# Sender_TransmiterPower.net
KiCad netlist of a schematic drawn in Altium Designer
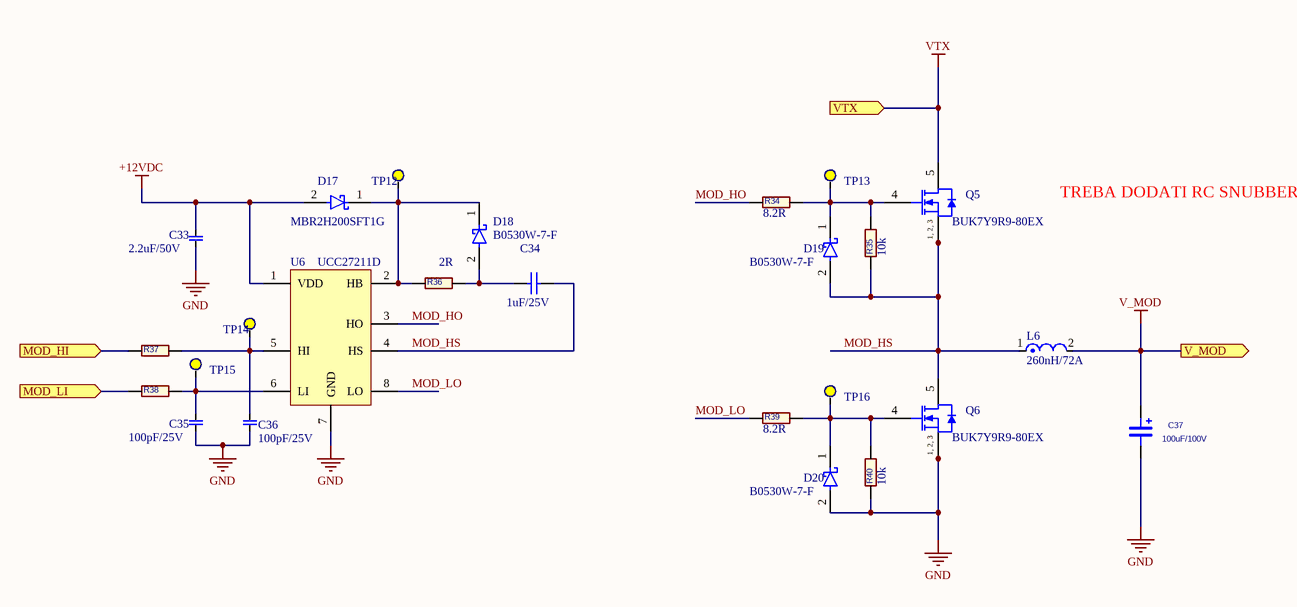
[diagram p0: Sender_TransmiterPower.SchDoc]

(export (version "E")
  (design (tool "Eeschema 10.0.6"))
  (components
    (comp (ref "C33")
      (value "2.2uF/50V")
      (footprint "FP-CL31-IPC_B")
      (description "Cap Ceramic 2.2uF 50V X7R ±10% SMD 1206 +125°C Embossed T/R")
      (fields (field (name "TOLERANCE") "10%"))
      (libsource (lib "New_Library") (part "CL31B225KBHVPNE"))
    )
    (comp (ref "C34")
      (value "1uF/25V")
      (footprint "CAPC2013X70X45LL10T25")
      (description "1µF ±10% 25V Ceramic Capacitor X5R 0805 (2012 Metric)")
      (fields (field (name "MANUFACTURER") "Murata") (field (name "PART NUMBER") "GRM216R61E105KA12D"))
      (libsource (lib "New_Library") (part "GRM216R61E105KA12D"))
    )
    (comp (ref "C35")
      (value "100pF/25V")
      (footprint "C-0603")
      (description "100pF ±5% 25V Ceramic Capacitor C0G, NP0 0201 (0603 Metric)")
      (fields
        (field (name "MANUFACTURER") "KEMET")
        (field (name "MANUFACTURER PART NUMBER") "C0201C101J3GACTU")
      )
      (libsource (lib "New_Library") (part "C0201C101J3GACTU"))
    )
    (comp (ref "C36")
      (value "100pF/25V")
      (footprint "C-0603")
      (description "100pF ±5% 25V Ceramic Capacitor C0G, NP0 0201 (0603 Metric)")
      (fields
        (field (name "MANUFACTURER") "KEMET")
        (field (name "MANUFACTURER PART NUMBER") "C0201C101J3GACTU")
      )
      (libsource (lib "New_Library") (part "C0201C101J3GACTU"))
    )
    (comp (ref "C37")
      (value "100uF/100V")
      (footprint "CAP_16X25")
      (description "Capacitor")
      (libsource (lib "New_Library") (part "CAP_470uF_100V"))
    )
    (comp (ref "D17")
      (value "MBR2H200SFT1G")
      (footprint "FP-498-MFG")
      (description "DIODE SCHOTTKY 200V 2A SOD123FL")
      (fields
        (field (name "MANUFACTURER") "ON Semiconductor")
        (field (name "OCTOPART") "https://octopart.com/mbr2h200sft1g-on+semiconductor-51167333")
      )
      (libsource (lib "New_Library") (part "MBR2H200SFT1G"))
    )
    (comp (ref "D18")
      (value "B0530W-7-F")
      (footprint "FP-SOD123-IPC_B")
      (description "DIODE SCHOTTKY 30V 500MA SOD123")
      (fields
        (field (name "MANUFACTURER") "Diodes Inc.")
        (field (name "OCTOPART") "https://octopart.com/b0530w-7-f-diodes+inc.-325721")
      )
      (libsource (lib "New_Library") (part "B0530W-7-F"))
    )
    (comp (ref "D19")
      (value "B0530W-7-F")
      (footprint "FP-SOD123-IPC_B")
      (description "DIODE SCHOTTKY 30V 500MA SOD123")
      (fields
        (field (name "MANUFACTURER") "Diodes Inc.")
        (field (name "OCTOPART") "https://octopart.com/b0530w-7-f-diodes+inc.-325721")
      )
      (libsource (lib "New_Library") (part "B0530W-7-F"))
    )
    (comp (ref "D20")
      (value "B0530W-7-F")
      (footprint "FP-SOD123-IPC_B")
      (description "DIODE SCHOTTKY 30V 500MA SOD123")
      (fields
        (field (name "MANUFACTURER") "Diodes Inc.")
        (field (name "OCTOPART") "https://octopart.com/b0530w-7-f-diodes+inc.-325721")
      )
      (libsource (lib "New_Library") (part "B0530W-7-F"))
    )
    (comp (ref "L6")
      (value "260nH/72A")
      (footprint "PA2891_FOOTPRINT")
      (description "260nH Shielded  Inductor 72A 0.22mOhm Nonstandard")
      (fields (field (name "TOLERANCE") "10%") (field (name "MANUFACTURER") "Pulse"))
      (libsource (lib "New_Library") (part "PA2891.261HL"))
    )
    (comp (ref "Q5")
      (value "BUK7Y9R9-80EX")
      (footprint "NXP-SOT669_N")
      (description "N-Channel 80V 89A (Tc) 195W (Tc) Surface Mount LFPAK56, Power-SO8")
      (fields (field (name "MANUFACTURER") "Nexperia"))
      (libsource (lib "New_Library") (part "BUK7Y9R9-80EX"))
    )
    (comp (ref "Q6")
      (value "BUK7Y9R9-80EX")
      (footprint "NXP-SOT669_N")
      (description "N-Channel 80V 89A (Tc) 195W (Tc) Surface Mount LFPAK56, Power-SO8")
      (fields (field (name "MANUFACTURER") "Nexperia"))
      (libsource (lib "New_Library") (part "BUK7Y9R9-80EX"))
    )
    (comp (ref "R34")
      (value "8.2R")
      (footprint "RES-0805")
      (description "8.2 Ohms ±5% 0.125W, 1/8W Chip Resistor 0805 (2012 Metric) Automotive AEC-Q200 Thick Film")
      (fields
        (field (name "MANUFACTURER") "Vishay Dale")
        (field (name "MANUFACTURER PART NUMBER") "CRCW08058R20JNEA")
      )
      (libsource (lib "New_Library") (part "CRCW08058R20JNEA"))
    )
    (comp (ref "R35")
      (value "10k")
      (footprint "R-0603")
      (description "10 kOhms ±0.5% 0.063W, 1/16W Chip Resistor 0603 (1608 Metric)  Thin Film")
      (fields
        (field (name "MANUFACTURER") "Susumu")
        (field (name "MANUFACTURER PART NUMBER") "RR0816P-103-D")
      )
      (libsource (lib "New_Library") (part "RR0816P-103-D"))
    )
    (comp (ref "R36")
      (value "2R")
      (footprint "RESC3216X60X45NL10T20")
      (description "2 Ohms ±1% 0.25W, 1/4W Chip Resistor 1206 (3216 Metric) Automotive AEC-Q200 Thick Film")
      (fields
        (field (name "MANUFACTURER") "Vishay Dale")
        (field (name "MANUFACTURER PART NUMBER") "CRCW12062R00FKEA")
      )
      (libsource (lib "New_Library") (part "CRCW12062R00FKEA"))
    )
    (comp (ref "R37")
      (value "1k")
      (footprint "R-0603")
      (description "1 kOhms ±0.5% 0.063W, 1/16W Chip Resistor 0603 (1608 Metric)  Thin Film")
      (fields
        (field (name "MANUFACTURER") "Susumu")
        (field (name "MANUFACTURER PART NUMBER") "RR0816P-102-D")
      )
      (libsource (lib "New_Library") (part "RR0816P-102-D"))
    )
    (comp (ref "R38")
      (value "1k")
      (footprint "R-0603")
      (description "1 kOhms ±0.5% 0.063W, 1/16W Chip Resistor 0603 (1608 Metric)  Thin Film")
      (fields
        (field (name "MANUFACTURER") "Susumu")
        (field (name "MANUFACTURER PART NUMBER") "RR0816P-102-D")
      )
      (libsource (lib "New_Library") (part "RR0816P-102-D"))
    )
    (comp (ref "R39")
      (value "8.2R")
      (footprint "RES-0805")
      (description "8.2 Ohms ±5% 0.125W, 1/8W Chip Resistor 0805 (2012 Metric) Automotive AEC-Q200 Thick Film")
      (fields
        (field (name "MANUFACTURER") "Vishay Dale")
        (field (name "MANUFACTURER PART NUMBER") "CRCW08058R20JNEA")
      )
      (libsource (lib "New_Library") (part "CRCW08058R20JNEA"))
    )
    (comp (ref "R40")
      (value "10k")
      (footprint "R-0603")
      (description "10 kOhms ±0.5% 0.063W, 1/16W Chip Resistor 0603 (1608 Metric)  Thin Film")
      (fields
        (field (name "MANUFACTURER") "Susumu")
        (field (name "MANUFACTURER PART NUMBER") "RR0816P-103-D")
      )
      (libsource (lib "New_Library") (part "RR0816P-103-D"))
    )
    (comp (ref "TP12")
      (value "Test_Point")
      (footprint "Test_Point")
      (libsource (lib "New_Library") (part "Test_Point"))
    )
    (comp (ref "TP13")
      (value "Test_Point")
      (footprint "Test_Point")
      (libsource (lib "New_Library") (part "Test_Point"))
    )
    (comp (ref "TP14")
      (value "Test_Point")
      (footprint "Test_Point")
      (libsource (lib "New_Library") (part "Test_Point"))
    )
    (comp (ref "TP15")
      (value "Test_Point")
      (footprint "Test_Point")
      (libsource (lib "New_Library") (part "Test_Point"))
    )
    (comp (ref "TP16")
      (value "Test_Point")
      (footprint "Test_Point")
      (libsource (lib "New_Library") (part "Test_Point"))
    )
    (comp (ref "U6")
      (value "UCC27211D")
      (footprint "D-8 PIN 1.27pitch")
      (description "Half-Bridge Gate Driver IC Non-Inverting 8-SOIC")
      (fields (field (name "MANUFACTURER") "Texas Instruments"))
      (libsource (lib "New_Library") (part "UCC27211D"))
    )
  )
  (nets
    (net (code "1") (name "+12VDC") (class "Default")
      (node (ref "C33") (pin "2") (pinfunction "G_2") (pintype "passive"))
      (node (ref "D17") (pin "2") (pinfunction "A_2") (pintype "passive"))
      (node (ref "U6") (pin "1") (pinfunction "VDD_1") (pintype "passive"))
    )
    (net (code "2") (name "/MOD_HI") (class "Default")
      (node (ref "R37") (pin "1") (pinfunction "1_1") (pintype "passive"))
    )
    (net (code "3") (name "/MOD_HO") (class "Default")
      (node (ref "R34") (pin "1") (pinfunction "1_1") (pintype "passive"))
      (node (ref "U6") (pin "3") (pinfunction "HO_3") (pintype "passive"))
    )
    (net (code "4") (name "/MOD_HS") (class "Default")
      (node (ref "C34") (pin "2") (pinfunction "2_2") (pintype "passive"))
      (node (ref "D19") (pin "2") (pinfunction "A_2") (pintype "passive"))
      (node (ref "L6") (pin "1") (pinfunction "1_1") (pintype "passive"))
      (node (ref "Q5") (pin "1") (pinfunction "S_1") (pintype "passive"))
      (node (ref "Q5") (pin "2") (pinfunction "S_2") (pintype "passive"))
      (node (ref "Q5") (pin "3") (pinfunction "S_3") (pintype "passive"))
      (node (ref "Q6") (pin "5") (pinfunction "D_5") (pintype "passive"))
      (node (ref "R35") (pin "1") (pinfunction "1_1") (pintype "passive"))
      (node (ref "U6") (pin "4") (pinfunction "HS_4") (pintype "passive"))
    )
    (net (code "5") (name "/MOD_LI") (class "Default")
      (node (ref "R38") (pin "1") (pinfunction "1_1") (pintype "passive"))
    )
    (net (code "6") (name "/MOD_LO") (class "Default")
      (node (ref "R39") (pin "1") (pinfunction "1_1") (pintype "passive"))
      (node (ref "U6") (pin "8") (pinfunction "LO_8") (pintype "passive"))
    )
    (net (code "7") (name "GND") (class "Default")
      (node (ref "C33") (pin "1") (pinfunction "G_1") (pintype "passive"))
      (node (ref "C35") (pin "1") (pinfunction "G_1") (pintype "passive"))
      (node (ref "C36") (pin "1") (pinfunction "G_1") (pintype "passive"))
      (node (ref "C37") (pin "2") (pinfunction "2_2") (pintype "passive"))
      (node (ref "D20") (pin "2") (pinfunction "A_2") (pintype "passive"))
      (node (ref "Q6") (pin "1") (pinfunction "S_1") (pintype "passive"))
      (node (ref "Q6") (pin "2") (pinfunction "S_2") (pintype "passive"))
      (node (ref "Q6") (pin "3") (pinfunction "S_3") (pintype "passive"))
      (node (ref "R40") (pin "1") (pinfunction "1_1") (pintype "passive"))
      (node (ref "U6") (pin "7") (pinfunction "GND_7") (pintype "passive"))
    )
    (net (code "8") (name "Net-(D17-C)") (class "Default")
      (node (ref "D17") (pin "1") (pinfunction "C_1") (pintype "passive"))
      (node (ref "D18") (pin "1") (pinfunction "C_1") (pintype "passive"))
      (node (ref "R36") (pin "1") (pinfunction "1_1") (pintype "passive"))
      (node (ref "TP12") (pin "1") (pinfunction "1_1") (pintype "passive"))
      (node (ref "U6") (pin "2") (pinfunction "HB_2") (pintype "passive"))
    )
    (net (code "9") (name "Net-(D18-A)") (class "Default")
      (node (ref "C34") (pin "1") (pinfunction "1_1") (pintype "passive"))
      (node (ref "D18") (pin "2") (pinfunction "A_2") (pintype "passive"))
      (node (ref "R36") (pin "2") (pinfunction "2_2") (pintype "passive"))
    )
    (net (code "10") (name "Net-(D19-C)") (class "Default")
      (node (ref "D19") (pin "1") (pinfunction "C_1") (pintype "passive"))
      (node (ref "Q5") (pin "4") (pinfunction "G_4") (pintype "passive"))
      (node (ref "R34") (pin "2") (pinfunction "2_2") (pintype "passive"))
      (node (ref "R35") (pin "2") (pinfunction "2_2") (pintype "passive"))
      (node (ref "TP13") (pin "1") (pinfunction "1_1") (pintype "passive"))
    )
    (net (code "11") (name "Net-(D20-C)") (class "Default")
      (node (ref "D20") (pin "1") (pinfunction "C_1") (pintype "passive"))
      (node (ref "Q6") (pin "4") (pinfunction "G_4") (pintype "passive"))
      (node (ref "R39") (pin "2") (pinfunction "2_2") (pintype "passive"))
      (node (ref "R40") (pin "2") (pinfunction "2_2") (pintype "passive"))
      (node (ref "TP16") (pin "1") (pinfunction "1_1") (pintype "passive"))
    )
    (net (code "12") (name "Net-(U6-HI)") (class "Default")
      (node (ref "C36") (pin "2") (pinfunction "G_2") (pintype "passive"))
      (node (ref "R37") (pin "2") (pinfunction "2_2") (pintype "passive"))
      (node (ref "TP14") (pin "1") (pinfunction "1_1") (pintype "passive"))
      (node (ref "U6") (pin "5") (pinfunction "HI_5") (pintype "passive"))
    )
    (net (code "13") (name "Net-(U6-LI)") (class "Default")
      (node (ref "C35") (pin "2") (pinfunction "G_2") (pintype "passive"))
      (node (ref "R38") (pin "2") (pinfunction "2_2") (pintype "passive"))
      (node (ref "TP15") (pin "1") (pinfunction "1_1") (pintype "passive"))
      (node (ref "U6") (pin "6") (pinfunction "LI_6") (pintype "passive"))
    )
    (net (code "14") (name "VTX") (class "Default")
      (node (ref "Q5") (pin "5") (pinfunction "D_5") (pintype "passive"))
    )
    (net (code "15") (name "V_MOD") (class "Default")
      (node (ref "C37") (pin "1") (pinfunction "1_1") (pintype "passive"))
      (node (ref "L6") (pin "2") (pinfunction "2_2") (pintype "passive"))
    )
  )
)
